# board1.net
KiCad netlist of a schematic drawn in Altium Designer
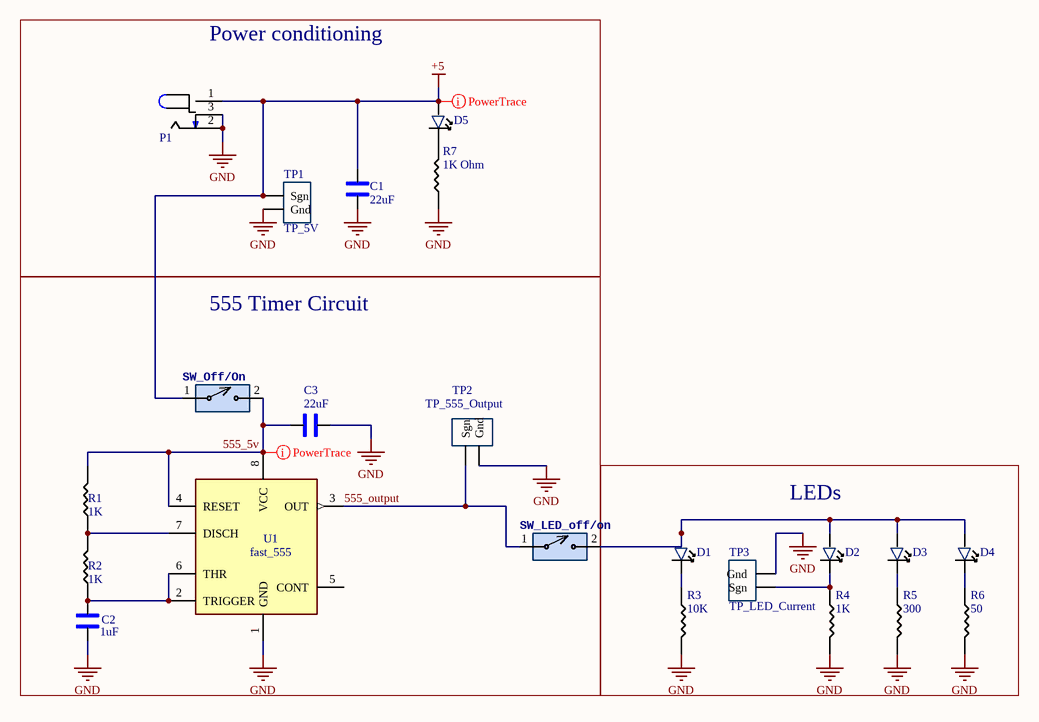
[diagram p0: board1.SchDoc]

(export (version "E")
  (design (tool "Eeschema 10.0.6"))
  (components
    (comp (ref "C1")
      (value "22uF")
      (footprint "1206_Passive_Capacitor")
      (description "22uF ±10% 25V X5R 1206 Multilayer Ceramic Capacitors MLCC - SMD/SMT RoHS")
      (fields (field (name "MFR PART #") "CL31A226KAHNNNE") (field (name "LCSC PART#") "C12891"))
      (libsource (lib "ECEN5730Lib_2023_05_DS") (part "C_22uF_1206"))
    )
    (comp (ref "C2")
      (value "1uF")
      (footprint "0402_Passive_Capacitor")
      (description "MULTILAYER CERAMIC CAPACITORS MLCC - SMD/SMT 1UF 25V 0402 ROHS")
      (fields (field (name "MFR PART #") "CL05A105KA5NQNC") (field (name "LCSC PART#") "C52923"))
      (libsource (lib "ECEN5730Lib_2023_05_DS") (part "C_1uF_0402"))
    )
    (comp (ref "C3")
      (value "22uF")
      (footprint "1206_Passive_Capacitor")
      (description "22uF ±10% 25V X5R 1206 Multilayer Ceramic Capacitors MLCC - SMD/SMT RoHS")
      (fields (field (name "MFR PART #") "CL31A226KAHNNNE") (field (name "LCSC PART#") "C12891"))
      (libsource (lib "ECEN5730Lib_2023_05_DS") (part "C_22uF_1206"))
    )
    (comp (ref "D1")
      (value "~")
      (footprint "LED_1206")
      (description "Red 621~631nm 1206 Light Emitting Diodes (LED) RoHS")
      (fields (field (name "MFR PART #") "15-21/R6C-FQ1R1B/2T") (field (name "LCSC PART#") "C93133"))
      (libsource (lib "ECEN5730Lib_2023_05_DS") (part "LED_RED_1206"))
    )
    (comp (ref "D2")
      (value "~")
      (footprint "LED_1206")
      (description "Red 621~631nm 1206 Light Emitting Diodes (LED) RoHS")
      (fields (field (name "MFR PART #") "15-21/R6C-FQ1R1B/2T") (field (name "LCSC PART#") "C93133"))
      (libsource (lib "ECEN5730Lib_2023_05_DS") (part "LED_RED_1206"))
    )
    (comp (ref "D3")
      (value "~")
      (footprint "LED_1206")
      (description "Red 621~631nm 1206 Light Emitting Diodes (LED) RoHS")
      (fields (field (name "MFR PART #") "15-21/R6C-FQ1R1B/2T") (field (name "LCSC PART#") "C93133"))
      (libsource (lib "ECEN5730Lib_2023_05_DS") (part "LED_RED_1206"))
    )
    (comp (ref "D4")
      (value "Red")
      (footprint "LED_1206")
      (description "Red 621~631nm 1206 Light Emitting Diodes (LED) RoHS")
      (fields (field (name "MFR PART #") "15-21/R6C-FQ1R1B/2T") (field (name "LCSC PART#") "C93133"))
      (libsource (lib "ECEN5730Lib_2023_05_DS") (part "LED_RED_1206"))
    )
    (comp (ref "D5")
      (value "Red")
      (footprint "LED_1206")
      (description "Red 621~631nm 1206 Light Emitting Diodes (LED) RoHS")
      (fields (field (name "MFR PART #") "15-21/R6C-FQ1R1B/2T") (field (name "LCSC PART#") "C93133"))
      (libsource (lib "ECEN5730Lib_2023_05_DS") (part "LED_RED_1206"))
    )
    (comp (ref "P1")
      (value "Power Jack")
      (footprint "Power_Jack")
      (description "Power Barrel Connector Jack 2.10mm ID (0.083\"), 5.50mm OD (0.217\") Through Hole, Right Angle")
      (fields (field (name "MFR PART #") "PJ-102A") (field (name "LCSC PART#") "C136744"))
      (libsource (lib "ECEN5730Lib_2023_05_DS") (part "P_Power Jack"))
    )
    (comp (ref "R1")
      (value "1K")
      (footprint "1206_Passive_Resitor")
      (description "CHIP RESISTOR - SURFACE MOUNT 1KOHMS ±1% 1/4W 1206 ROHS")
      (fields (field (name "MFR PART #") "RNCP1206FTD1K00CT") (field (name "LCSC PART#") "C4410"))
      (libsource (lib "ECEN5730Lib_2023_05_DS") (part "R_1K_1206"))
    )
    (comp (ref "R2")
      (value "1K")
      (footprint "1206_Passive_Resitor")
      (description "CHIP RESISTOR - SURFACE MOUNT 1KOHMS ±1% 1/4W 1206 ROHS")
      (fields (field (name "MFR PART #") "RNCP1206FTD1K00CT") (field (name "LCSC PART#") "C4410"))
      (libsource (lib "ECEN5730Lib_2023_05_DS") (part "R_1K_1206"))
    )
    (comp (ref "R3")
      (value "10K")
      (footprint "1206_Passive_Resitor")
      (description "CHIP RESISTOR - SURFACE MOUNT 1MOHMS ±1% 1/4W 1206 ROHS")
      (fields (field (name "MFR PART #") "RMCF1206JT1M00") (field (name "LCSC PART#") "C17927"))
      (libsource (lib "ECEN5730Lib_2023_05_DS") (part "R_1M_1206"))
    )
    (comp (ref "R4")
      (value "1K")
      (footprint "1206_Passive_Resitor")
      (description "CHIP RESISTOR - SURFACE MOUNT 1KOHMS ±1% 1/4W 1206 ROHS")
      (fields (field (name "MFR PART #") "RNCP1206FTD1K00CT") (field (name "LCSC PART#") "C4410"))
      (libsource (lib "ECEN5730Lib_2023_05_DS") (part "R_1K_1206"))
    )
    (comp (ref "R5")
      (value "300")
      (footprint "1206_Passive_Resitor")
      (description "CHIP RESISTOR - SURFACE MOUNT 300OHMS ±1% 1/4W 1206 ROHS")
      (fields (field (name "MFR PART #") "1206W4F3000T5E") (field (name "LCSC PART#") "C17887"))
      (libsource (lib "ECEN5730Lib_2023_05_DS") (part "R_300Ohm_1206"))
    )
    (comp (ref "R6")
      (value "50")
      (footprint "1206_Passive_Resitor")
      (description "CHIP RESISTOR - SURFACE MOUNT 1KOHMS ±1% 1/4W 1206 ROHS")
      (fields (field (name "MFR PART #") "RNCP1206FTD1K00CT") (field (name "LCSC PART#") "C4410"))
      (libsource (lib "ECEN5730Lib_2023_05_DS") (part "R_1K_1206"))
    )
    (comp (ref "R7")
      (value "1K Ohm")
      (footprint "1206_Passive_Resitor")
      (description "CHIP RESISTOR - SURFACE MOUNT 1KOHMS ±1% 1/4W 1206 ROHS")
      (fields (field (name "MFR PART #") "RNCP1206FTD1K00CT") (field (name "LCSC PART#") "C4410"))
      (libsource (lib "ECEN5730Lib_2023_05_DS") (part "R_1K_1206"))
    )
    (comp (ref "SW_LED_off/on")
      (value "SW_2Pin_100mil_Switch")
      (footprint "2Pin-Header-Conn")
      (description "2Pin Header")
      (fields (field (name "LCSC PART#") "C124375"))
      (libsource (lib "ECEN5730Lib_2023_05_DS") (part "SW_2Pin_100mil_Switch"))
    )
    (comp (ref "SW_Off/On")
      (value "SW_2Pin_100mil_Switch")
      (footprint "2Pin-Header-Conn")
      (description "2Pin Header")
      (fields (field (name "LCSC PART#") "C124375"))
      (libsource (lib "ECEN5730Lib_2023_05_DS") (part "SW_2Pin_100mil_Switch"))
    )
    (comp (ref "TP1")
      (value "TP_5V")
      (footprint "TP10x_Probe")
      (description "Test Point 300 mil centers")
      (libsource (lib "") (part "TP_10x_Probe_2"))
    )
    (comp (ref "TP2")
      (value "TP_555_Output")
      (footprint "TP10x_Probe")
      (description "Test Point 300 mil centers")
      (libsource (lib "") (part "TP_10x_Probe_1"))
    )
    (comp (ref "TP3")
      (value "TP_LED_Current")
      (footprint "TP10x_Probe")
      (description "Test Point 300 mil centers")
      (libsource (lib "ECEN5730Lib_2023_05_DS") (part "TP_10x_Probe"))
    )
    (comp (ref "U1")
      (value "fast_555")
      (footprint "TS555IDTTR")
      (description "555 Type, Timer/Oscillator _Single_ IC 3MHz 8-SO")
      (fields (field (name "MFR PART #") "LMC555CMX/NOPB") (field (name "LCSC PART#") "C90760"))
      (libsource (lib "ECEN5730Lib_2023_05_DS") (part "U_555_Fast"))
    )
  )
  (nets
    (net (code "1") (name "+5") (class "Default")
      (node (ref "C1") (pin "1") (pinfunction "1_1") (pintype "passive"))
      (node (ref "D5") (pin "1") (pinfunction "1_1") (pintype "passive"))
      (node (ref "P1") (pin "1") (pinfunction "1_1") (pintype "power_in"))
      (node (ref "SW_Off/On") (pin "1") (pinfunction "1_1") (pintype "passive"))
      (node (ref "TP1") (pin "1") (pinfunction "Sgn_1") (pintype "passive"))
    )
    (net (code "2") (name "/555_5v") (class "Default")
      (node (ref "C3") (pin "1") (pinfunction "1_1") (pintype "passive"))
      (node (ref "R1") (pin "2") (pinfunction "2_2") (pintype "passive"))
      (node (ref "SW_Off/On") (pin "2") (pinfunction "2_2") (pintype "passive"))
      (node (ref "U1") (pin "4") (pinfunction "RESET_4") (pintype "passive"))
      (node (ref "U1") (pin "8") (pinfunction "VCC_8") (pintype "power_in"))
    )
    (net (code "3") (name "/555_output") (class "Default")
      (node (ref "SW_LED_off/on") (pin "1") (pinfunction "1_1") (pintype "passive"))
      (node (ref "TP2") (pin "1") (pinfunction "Sgn_1") (pintype "passive"))
      (node (ref "U1") (pin "3") (pinfunction "OUT_3") (pintype "output"))
    )
    (net (code "5") (name "GND") (class "Default")
      (node (ref "C1") (pin "2") (pinfunction "2_2") (pintype "passive"))
      (node (ref "C2") (pin "2") (pinfunction "2_2") (pintype "passive"))
      (node (ref "C3") (pin "2") (pinfunction "2_2") (pintype "passive"))
      (node (ref "P1") (pin "2") (pinfunction "2_2") (pintype "power_in"))
      (node (ref "P1") (pin "3") (pinfunction "3_3") (pintype "power_in"))
      (node (ref "R3") (pin "2") (pinfunction "2_2") (pintype "passive"))
      (node (ref "R4") (pin "2") (pinfunction "2_2") (pintype "passive"))
      (node (ref "R5") (pin "2") (pinfunction "2_2") (pintype "passive"))
      (node (ref "R6") (pin "2") (pinfunction "2_2") (pintype "passive"))
      (node (ref "R7") (pin "1") (pinfunction "1_1") (pintype "passive"))
      (node (ref "TP1") (pin "2") (pinfunction "Gnd_2") (pintype "passive"))
      (node (ref "TP2") (pin "2") (pinfunction "Gnd_2") (pintype "passive"))
      (node (ref "TP3") (pin "2") (pinfunction "Gnd_2") (pintype "passive"))
      (node (ref "U1") (pin "1") (pinfunction "GND_1") (pintype "power_in"))
    )
    (net (code "6") (name "Net-(D1-Pad1)") (class "Default")
      (node (ref "D1") (pin "1") (pinfunction "1_1") (pintype "passive"))
      (node (ref "D2") (pin "1") (pinfunction "1_1") (pintype "passive"))
      (node (ref "D3") (pin "1") (pinfunction "1_1") (pintype "passive"))
      (node (ref "D4") (pin "1") (pinfunction "1_1") (pintype "passive"))
      (node (ref "SW_LED_off/on") (pin "2") (pinfunction "2_2") (pintype "passive"))
    )
    (net (code "7") (name "Net-(D1-Pad2)") (class "Default")
      (node (ref "D1") (pin "2") (pinfunction "2_2") (pintype "passive"))
      (node (ref "R3") (pin "1") (pinfunction "1_1") (pintype "passive"))
    )
    (net (code "8") (name "Net-(D3-Pad2)") (class "Default")
      (node (ref "D3") (pin "2") (pinfunction "2_2") (pintype "passive"))
      (node (ref "R5") (pin "1") (pinfunction "1_1") (pintype "passive"))
    )
    (net (code "9") (name "Net-(D4-Pad2)") (class "Default")
      (node (ref "D4") (pin "2") (pinfunction "2_2") (pintype "passive"))
      (node (ref "R6") (pin "1") (pinfunction "1_1") (pintype "passive"))
    )
    (net (code "10") (name "Net-(D5-Pad2)") (class "Default")
      (node (ref "D5") (pin "2") (pinfunction "2_2") (pintype "passive"))
      (node (ref "R7") (pin "2") (pinfunction "2_2") (pintype "passive"))
    )
    (net (code "11") (name "Net-(TP3-Sgn)") (class "Default")
      (node (ref "D2") (pin "2") (pinfunction "2_2") (pintype "passive"))
      (node (ref "R4") (pin "1") (pinfunction "1_1") (pintype "passive"))
      (node (ref "TP3") (pin "1") (pinfunction "Sgn_1") (pintype "passive"))
    )
    (net (code "12") (name "Net-(U1-DISCH)") (class "Default")
      (node (ref "R1") (pin "1") (pinfunction "1_1") (pintype "passive"))
      (node (ref "R2") (pin "2") (pinfunction "2_2") (pintype "passive"))
      (node (ref "U1") (pin "7") (pinfunction "DISCH_7") (pintype "passive"))
    )
    (net (code "13") (name "Net-(U1-THR)") (class "Default")
      (node (ref "C2") (pin "1") (pinfunction "1_1") (pintype "passive"))
      (node (ref "R2") (pin "1") (pinfunction "1_1") (pintype "passive"))
      (node (ref "U1") (pin "2") (pinfunction "TRIGGER_2") (pintype "passive"))
      (node (ref "U1") (pin "6") (pinfunction "THR_6") (pintype "passive"))
    )
    (net (code "14") (name "unconnected-(U1-CONT-Pad5)") (class "Default")
      (node (ref "U1") (pin "5") (pinfunction "CONT_5") (pintype "passive"))
    )
  )
)
